# Protoboard_FeatherWing_A1_Rev_01.net
KiCad netlist of a schematic drawn in EAGLE
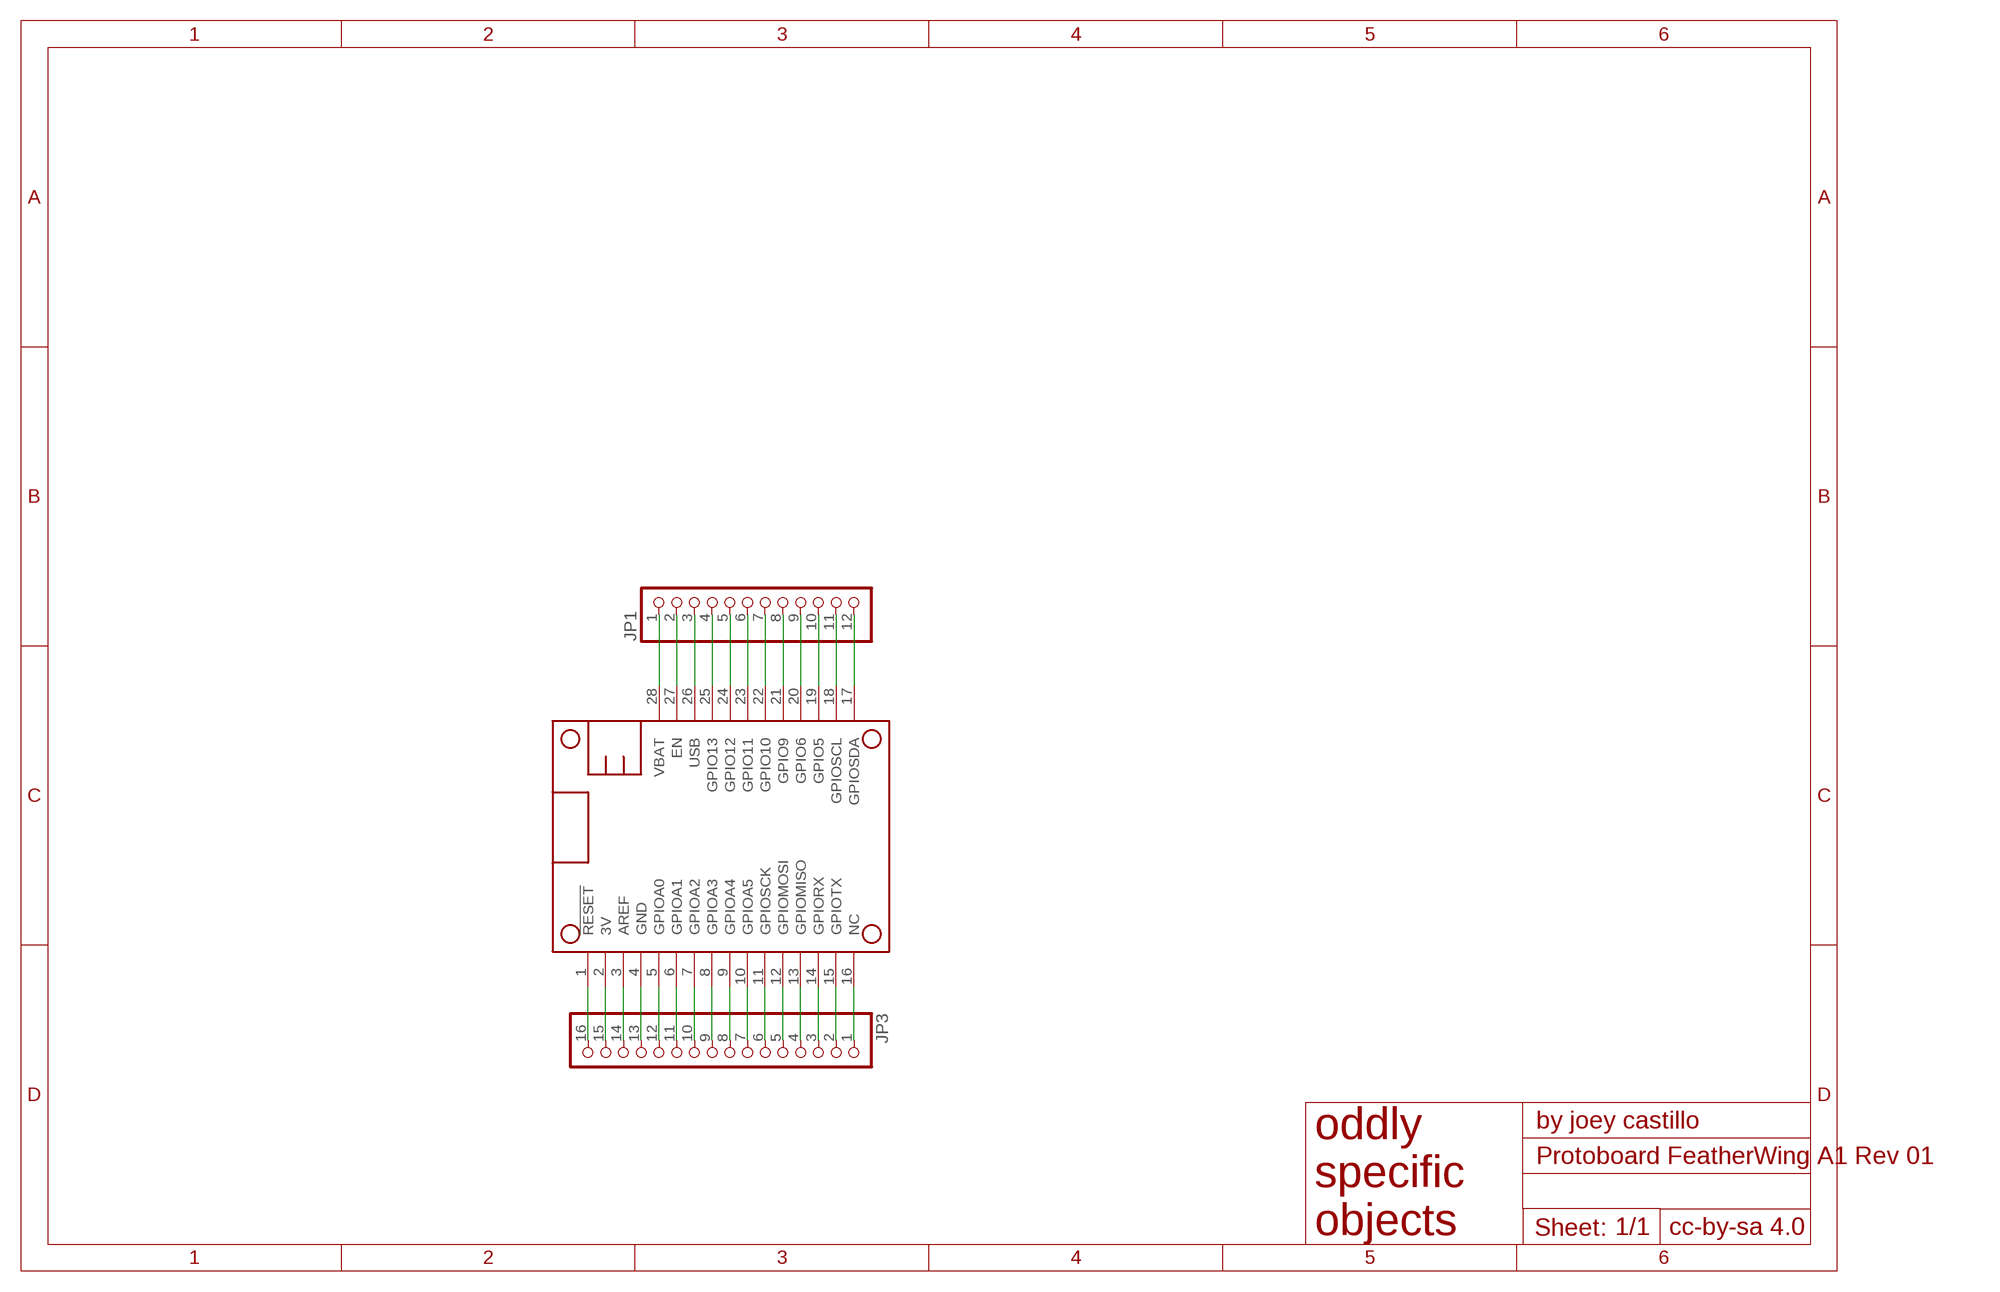
[diagram p0: schematic, sheet 1]

(export (version "E")
  (design (tool "Eeschema 10.0.6"))
  (components
    (comp (ref "JP1")
      (value "HEADER-1X1276MIL")
      (footprint "eagle-import:1X12_ROUND_76MIL")
      (libsource (lib "eagle-import") (part "HEADER-1X1276MIL"))
    )
    (comp (ref "JP3")
      (value "HEADER-1X16_76MIL")
      (footprint "eagle-import:1X16_ROUND_76MIL")
      (libsource (lib "eagle-import") (part "HEADER-1X16_76MIL"))
    )
    (comp (ref "MS1")
      (value "FEATHERWING")
      (footprint "eagle-import:FEATHERWING")
      (libsource (lib "eagle-import") (part "FEATHERWING"))
    )
  )
  (nets
    (net (code "1") (name "Net-(MS1-3V)") (class "Default")
      (node (ref "JP3") (pin "15") (pinfunction "15_15") (pintype "passive"))
      (node (ref "MS1") (pin "2") (pinfunction "3V_2") (pintype "power_in"))
    )
    (net (code "2") (name "Net-(MS1-AREF)") (class "Default")
      (node (ref "JP3") (pin "14") (pinfunction "14_14") (pintype "passive"))
      (node (ref "MS1") (pin "3") (pinfunction "AREF_3") (pintype "passive"))
    )
    (net (code "3") (name "Net-(MS1-EN)") (class "Default")
      (node (ref "JP1") (pin "2") (pinfunction "2_2") (pintype "passive"))
      (node (ref "MS1") (pin "27") (pinfunction "EN_27") (pintype "passive"))
    )
    (net (code "4") (name "Net-(MS1-GND)") (class "Default")
      (node (ref "JP3") (pin "13") (pinfunction "13_13") (pintype "passive"))
      (node (ref "MS1") (pin "4") (pinfunction "GND_4") (pintype "power_in"))
    )
    (net (code "5") (name "Net-(MS1-GPIO5)") (class "Default")
      (node (ref "JP1") (pin "10") (pinfunction "10_10") (pintype "passive"))
      (node (ref "MS1") (pin "19") (pinfunction "GPIO5_19") (pintype "bidirectional"))
    )
    (net (code "6") (name "Net-(MS1-GPIO6)") (class "Default")
      (node (ref "JP1") (pin "9") (pinfunction "9_9") (pintype "passive"))
      (node (ref "MS1") (pin "20") (pinfunction "GPIO6_20") (pintype "bidirectional"))
    )
    (net (code "7") (name "Net-(MS1-GPIO9)") (class "Default")
      (node (ref "JP1") (pin "8") (pinfunction "8_8") (pintype "passive"))
      (node (ref "MS1") (pin "21") (pinfunction "GPIO9_21") (pintype "bidirectional"))
    )
    (net (code "8") (name "Net-(MS1-GPIO10)") (class "Default")
      (node (ref "JP1") (pin "7") (pinfunction "7_7") (pintype "passive"))
      (node (ref "MS1") (pin "22") (pinfunction "GPIO10_22") (pintype "bidirectional"))
    )
    (net (code "9") (name "Net-(MS1-GPIO11)") (class "Default")
      (node (ref "JP1") (pin "6") (pinfunction "6_6") (pintype "passive"))
      (node (ref "MS1") (pin "23") (pinfunction "GPIO11_23") (pintype "bidirectional"))
    )
    (net (code "10") (name "Net-(MS1-GPIO12)") (class "Default")
      (node (ref "JP1") (pin "5") (pinfunction "5_5") (pintype "passive"))
      (node (ref "MS1") (pin "24") (pinfunction "GPIO12_24") (pintype "bidirectional"))
    )
    (net (code "11") (name "Net-(MS1-GPIO13)") (class "Default")
      (node (ref "JP1") (pin "4") (pinfunction "4_4") (pintype "passive"))
      (node (ref "MS1") (pin "25") (pinfunction "GPIO13_25") (pintype "bidirectional"))
    )
    (net (code "12") (name "Net-(MS1-GPIOA0)") (class "Default")
      (node (ref "JP3") (pin "12") (pinfunction "12_12") (pintype "passive"))
      (node (ref "MS1") (pin "5") (pinfunction "GPIOA0_5") (pintype "bidirectional"))
    )
    (net (code "13") (name "Net-(MS1-GPIOA1)") (class "Default")
      (node (ref "JP3") (pin "11") (pinfunction "11_11") (pintype "passive"))
      (node (ref "MS1") (pin "6") (pinfunction "GPIOA1_6") (pintype "bidirectional"))
    )
    (net (code "14") (name "Net-(MS1-GPIOA2)") (class "Default")
      (node (ref "JP3") (pin "10") (pinfunction "10_10") (pintype "passive"))
      (node (ref "MS1") (pin "7") (pinfunction "GPIOA2_7") (pintype "bidirectional"))
    )
    (net (code "15") (name "Net-(MS1-GPIOA3)") (class "Default")
      (node (ref "JP3") (pin "9") (pinfunction "9_9") (pintype "passive"))
      (node (ref "MS1") (pin "8") (pinfunction "GPIOA3_8") (pintype "bidirectional"))
    )
    (net (code "16") (name "Net-(MS1-GPIOA4)") (class "Default")
      (node (ref "JP3") (pin "8") (pinfunction "8_8") (pintype "passive"))
      (node (ref "MS1") (pin "9") (pinfunction "GPIOA4_9") (pintype "bidirectional"))
    )
    (net (code "17") (name "Net-(MS1-GPIOA5)") (class "Default")
      (node (ref "JP3") (pin "7") (pinfunction "7_7") (pintype "passive"))
      (node (ref "MS1") (pin "10") (pinfunction "GPIOA5_10") (pintype "bidirectional"))
    )
    (net (code "18") (name "Net-(MS1-GPIOMISO)") (class "Default")
      (node (ref "JP3") (pin "4") (pinfunction "4_4") (pintype "passive"))
      (node (ref "MS1") (pin "13") (pinfunction "GPIOMISO_13") (pintype "bidirectional"))
    )
    (net (code "19") (name "Net-(MS1-GPIOMOSI)") (class "Default")
      (node (ref "JP3") (pin "5") (pinfunction "5_5") (pintype "passive"))
      (node (ref "MS1") (pin "12") (pinfunction "GPIOMOSI_12") (pintype "bidirectional"))
    )
    (net (code "20") (name "Net-(MS1-GPIORX)") (class "Default")
      (node (ref "JP3") (pin "3") (pinfunction "3_3") (pintype "passive"))
      (node (ref "MS1") (pin "14") (pinfunction "GPIORX_14") (pintype "bidirectional"))
    )
    (net (code "21") (name "Net-(MS1-GPIOSCK)") (class "Default")
      (node (ref "JP3") (pin "6") (pinfunction "6_6") (pintype "passive"))
      (node (ref "MS1") (pin "11") (pinfunction "GPIOSCK_11") (pintype "bidirectional"))
    )
    (net (code "22") (name "Net-(MS1-GPIOSCL)") (class "Default")
      (node (ref "JP1") (pin "11") (pinfunction "11_11") (pintype "passive"))
      (node (ref "MS1") (pin "18") (pinfunction "GPIOSCL_18") (pintype "bidirectional"))
    )
    (net (code "23") (name "Net-(MS1-GPIOSDA)") (class "Default")
      (node (ref "JP1") (pin "12") (pinfunction "12_12") (pintype "passive"))
      (node (ref "MS1") (pin "17") (pinfunction "GPIOSDA_17") (pintype "bidirectional"))
    )
    (net (code "24") (name "Net-(MS1-GPIOTX)") (class "Default")
      (node (ref "JP3") (pin "2") (pinfunction "2_2") (pintype "passive"))
      (node (ref "MS1") (pin "15") (pinfunction "GPIOTX_15") (pintype "bidirectional"))
    )
    (net (code "25") (name "Net-(MS1-NC)") (class "Default")
      (node (ref "JP3") (pin "1") (pinfunction "1_1") (pintype "passive"))
      (node (ref "MS1") (pin "16") (pinfunction "NC_16") (pintype "passive"))
    )
    (net (code "26") (name "Net-(MS1-USB)") (class "Default")
      (node (ref "JP1") (pin "3") (pinfunction "3_3") (pintype "passive"))
      (node (ref "MS1") (pin "26") (pinfunction "USB_26") (pintype "power_in"))
    )
    (net (code "27") (name "Net-(MS1-VBAT)") (class "Default")
      (node (ref "JP1") (pin "1") (pinfunction "1_1") (pintype "passive"))
      (node (ref "MS1") (pin "28") (pinfunction "VBAT_28") (pintype "power_in"))
    )
    (net (code "28") (name "Net-(MS1-~{RESET})") (class "Default")
      (node (ref "JP3") (pin "16") (pinfunction "16_16") (pintype "passive"))
      (node (ref "MS1") (pin "1") (pinfunction "~{RESET}_1") (pintype "input"))
    )
  )
)
